# VLC_RX_Schem.net
KiCad netlist of a schematic drawn in Altium Designer
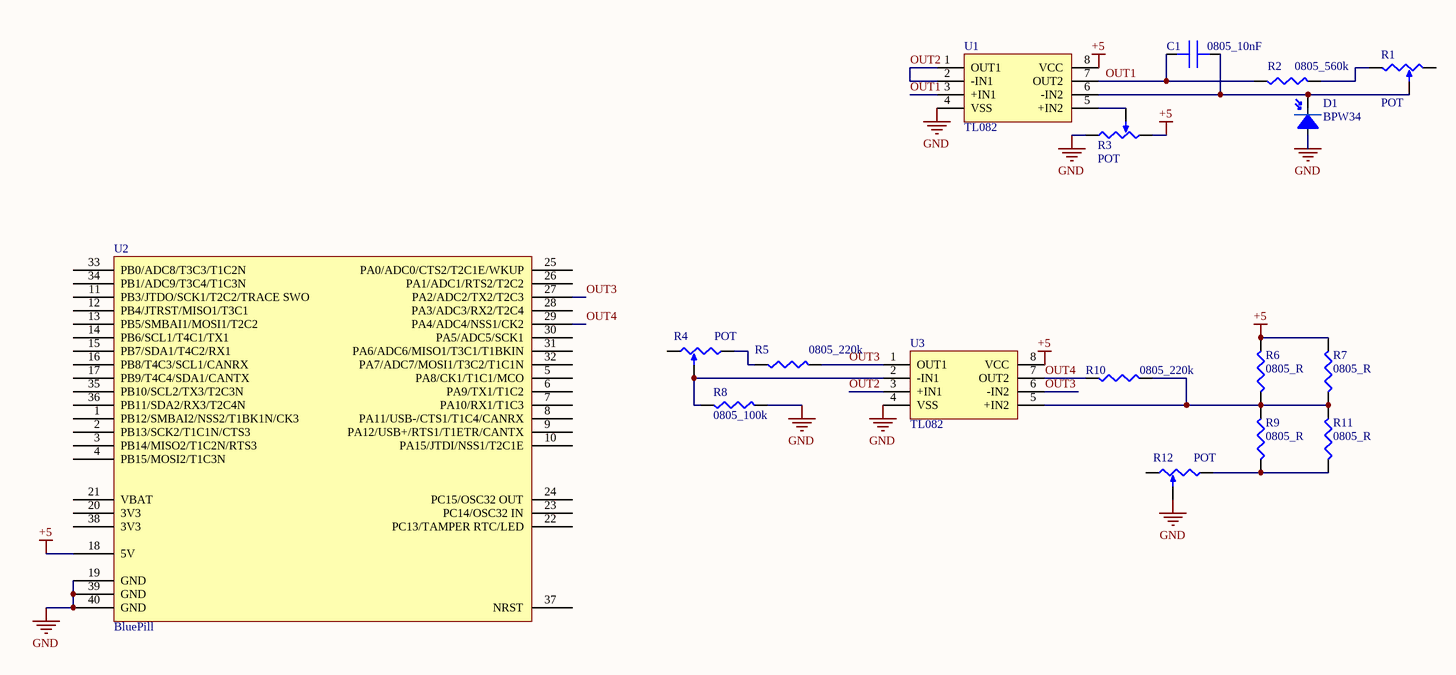
[diagram p0: VLC_RX_Schem.SchDoc]

(export (version "E")
  (design (tool "Eeschema 10.0.6"))
  (components
    (comp (ref "C1")
      (value "0805_10nF")
      (footprint "C0805 - 0.1uf")
      (description "0805 Capacitor")
      (libsource (lib "TimerSMD_Components") (part "0805 Capacitor"))
    )
    (comp (ref "D1") (value "BPW34") (footprint "BPW34") (libsource (lib "CAD_Symbols") (part "BPW34")))
    (comp (ref "R1") (value "POT") (footprint "POT 3386P") (libsource (lib "CAD_Symbols") (part "POT")))
    (comp (ref "R2")
      (value "0805_560k")
      (footprint "R0805")
      (libsource (lib "TimerSMD_Components") (part "0805 Resistor"))
    )
    (comp (ref "R3") (value "POT") (footprint "POT 3386P") (libsource (lib "CAD_Symbols") (part "POT")))
    (comp (ref "R4") (value "POT") (footprint "POT 3386P") (libsource (lib "CAD_Symbols") (part "POT")))
    (comp (ref "R5")
      (value "0805_220k")
      (footprint "R0805")
      (libsource (lib "TimerSMD_Components") (part "0805 Resistor"))
    )
    (comp (ref "R6")
      (value "0805_R")
      (footprint "R0805")
      (libsource (lib "TimerSMD_Components") (part "0805 Resistor"))
    )
    (comp (ref "R7")
      (value "0805_R")
      (footprint "R0805")
      (libsource (lib "TimerSMD_Components") (part "0805 Resistor"))
    )
    (comp (ref "R8")
      (value "0805_100k")
      (footprint "R0805")
      (libsource (lib "TimerSMD_Components") (part "0805 Resistor"))
    )
    (comp (ref "R9")
      (value "0805_R")
      (footprint "R0805")
      (libsource (lib "TimerSMD_Components") (part "0805 Resistor"))
    )
    (comp (ref "R10")
      (value "0805_220k")
      (footprint "R0805")
      (libsource (lib "TimerSMD_Components") (part "0805 Resistor"))
    )
    (comp (ref "R11")
      (value "0805_R")
      (footprint "R0805")
      (libsource (lib "TimerSMD_Components") (part "0805 Resistor"))
    )
    (comp (ref "R12") (value "POT") (footprint "POT 3386P") (libsource (lib "CAD_Symbols") (part "POT")))
    (comp (ref "U1")
      (value "TL082")
      (footprint "SOP8")
      (description "TL082CD SO-8 Operational Amplifier SMD IC")
      (libsource (lib "TimerSMD_Components") (part "TL082"))
    )
    (comp (ref "U2")
      (value "BluePill")
      (footprint "BluePill")
      (libsource (lib "CAD_Symbols") (part "STM32 BluePill"))
    )
    (comp (ref "U3")
      (value "TL082")
      (footprint "SOP8")
      (description "TL082CD SO-8 Operational Amplifier SMD IC")
      (libsource (lib "TimerSMD_Components") (part "TL082"))
    )
  )
  (nets
    (net (code "1") (name "+5") (class "Default")
      (node (ref "R3") (pin "1") (pinfunction "1_1") (pintype "passive"))
      (node (ref "R6") (pin "1") (pinfunction "1_1") (pintype "passive"))
      (node (ref "R7") (pin "1") (pinfunction "1_1") (pintype "passive"))
      (node (ref "U1") (pin "8") (pinfunction "VCC_8") (pintype "passive"))
      (node (ref "U2") (pin "18") (pinfunction "5V_18") (pintype "passive"))
      (node (ref "U3") (pin "8") (pinfunction "VCC_8") (pintype "passive"))
    )
    (net (code "2") (name "/OUT1") (class "Default")
      (node (ref "C1") (pin "1") (pinfunction "1_1") (pintype "passive"))
      (node (ref "R2") (pin "1") (pinfunction "1_1") (pintype "passive"))
      (node (ref "U1") (pin "3") (pinfunction "+IN1_3") (pintype "passive"))
      (node (ref "U1") (pin "7") (pinfunction "OUT2_7") (pintype "passive"))
    )
    (net (code "3") (name "/OUT2") (class "Default")
      (node (ref "U1") (pin "1") (pinfunction "OUT1_1") (pintype "passive"))
      (node (ref "U1") (pin "2") (pinfunction "-IN1_2") (pintype "passive"))
      (node (ref "U3") (pin "3") (pinfunction "+IN1_3") (pintype "passive"))
    )
    (net (code "4") (name "/OUT3") (class "Default")
      (node (ref "R5") (pin "1") (pinfunction "1_1") (pintype "passive"))
      (node (ref "U2") (pin "27") (pinfunction "PA2/ADC2/TX2/T2C3_27") (pintype "passive"))
      (node (ref "U3") (pin "1") (pinfunction "OUT1_1") (pintype "passive"))
      (node (ref "U3") (pin "6") (pinfunction "-IN2_6") (pintype "passive"))
    )
    (net (code "5") (name "/OUT4") (class "Default")
      (node (ref "R10") (pin "1") (pinfunction "1_1") (pintype "passive"))
      (node (ref "U2") (pin "29") (pinfunction "PA4/ADC4/NSS1/CK2_29") (pintype "passive"))
      (node (ref "U3") (pin "7") (pinfunction "OUT2_7") (pintype "passive"))
    )
    (net (code "6") (name "GND") (class "Default")
      (node (ref "D1") (pin "A") (pinfunction "Anode_A") (pintype "passive"))
      (node (ref "R12") (pin "3") (pinfunction "3_3") (pintype "passive"))
      (node (ref "R3") (pin "2") (pinfunction "2_2") (pintype "passive"))
      (node (ref "R8") (pin "2") (pinfunction "2_2") (pintype "passive"))
      (node (ref "U1") (pin "4") (pinfunction "VSS_4") (pintype "passive"))
      (node (ref "U2") (pin "19") (pinfunction "GND_19") (pintype "passive"))
      (node (ref "U2") (pin "39") (pinfunction "GND_39") (pintype "passive"))
      (node (ref "U2") (pin "40") (pinfunction "GND_40") (pintype "passive"))
      (node (ref "U3") (pin "4") (pinfunction "VSS_4") (pintype "passive"))
    )
    (net (code "7") (name "Net-(D1-Cathode)") (class "Default")
      (node (ref "C1") (pin "2") (pinfunction "2_2") (pintype "passive"))
      (node (ref "D1") (pin "K") (pinfunction "Cathode_K") (pintype "passive"))
      (node (ref "R1") (pin "3") (pinfunction "3_3") (pintype "passive"))
      (node (ref "U1") (pin "6") (pinfunction "-IN2_6") (pintype "passive"))
    )
    (net (code "8") (name "Net-(R1-Pad2)") (class "Default")
      (node (ref "R1") (pin "2") (pinfunction "2_2") (pintype "passive"))
      (node (ref "R2") (pin "2") (pinfunction "2_2") (pintype "passive"))
    )
    (net (code "9") (name "Net-(R4-Pad2)") (class "Default")
      (node (ref "R4") (pin "2") (pinfunction "2_2") (pintype "passive"))
      (node (ref "R5") (pin "2") (pinfunction "2_2") (pintype "passive"))
    )
    (net (code "10") (name "Net-(R11-Pad2)") (class "Default")
      (node (ref "R11") (pin "2") (pinfunction "2_2") (pintype "passive"))
      (node (ref "R12") (pin "2") (pinfunction "2_2") (pintype "passive"))
      (node (ref "R9") (pin "2") (pinfunction "2_2") (pintype "passive"))
    )
    (net (code "11") (name "Net-(U1-+IN2)") (class "Default")
      (node (ref "R3") (pin "3") (pinfunction "3_3") (pintype "passive"))
      (node (ref "U1") (pin "5") (pinfunction "+IN2_5") (pintype "passive"))
    )
    (net (code "12") (name "Net-(U3-+IN2)") (class "Default")
      (node (ref "R10") (pin "2") (pinfunction "2_2") (pintype "passive"))
      (node (ref "R11") (pin "1") (pinfunction "1_1") (pintype "passive"))
      (node (ref "R6") (pin "2") (pinfunction "2_2") (pintype "passive"))
      (node (ref "R7") (pin "2") (pinfunction "2_2") (pintype "passive"))
      (node (ref "R9") (pin "1") (pinfunction "1_1") (pintype "passive"))
      (node (ref "U3") (pin "5") (pinfunction "+IN2_5") (pintype "passive"))
    )
    (net (code "13") (name "Net-(U3--IN1)") (class "Default")
      (node (ref "R4") (pin "3") (pinfunction "3_3") (pintype "passive"))
      (node (ref "R8") (pin "1") (pinfunction "1_1") (pintype "passive"))
      (node (ref "U3") (pin "2") (pinfunction "-IN1_2") (pintype "passive"))
    )
    (net (code "14") (name "unconnected-(R1-Pad1)") (class "Default")
      (node (ref "R1") (pin "1") (pinfunction "1_1") (pintype "passive"))
    )
    (net (code "15") (name "unconnected-(R4-Pad1)") (class "Default")
      (node (ref "R4") (pin "1") (pinfunction "1_1") (pintype "passive"))
    )
    (net (code "16") (name "unconnected-(R12-Pad1)") (class "Default")
      (node (ref "R12") (pin "1") (pinfunction "1_1") (pintype "passive"))
    )
    (net (code "17") (name "unconnected-(U2-3V3-Pad20)") (class "Default")
      (node (ref "U2") (pin "20") (pinfunction "3V3_20") (pintype "passive"))
    )
    (net (code "18") (name "unconnected-(U2-3V3-Pad38)") (class "Default")
      (node (ref "U2") (pin "38") (pinfunction "3V3_38") (pintype "passive"))
    )
    (net (code "19") (name "unconnected-(U2-NRST-Pad37)") (class "Default")
      (node (ref "U2") (pin "37") (pinfunction "NRST_37") (pintype "passive"))
    )
    (net (code "20") (name "unconnected-(U2-PA0{slash}ADC0{slash}CTS2{slash}T2C1E{slash}WKUP-Pad25)") (class "Default")
      (node (ref "U2") (pin "25") (pinfunction "PA0/ADC0/CTS2/T2C1E/WKUP_25") (pintype "passive"))
    )
    (net (code "21") (name "unconnected-(U2-PA1{slash}ADC1{slash}RTS2{slash}T2C2-Pad26)") (class "Default")
      (node (ref "U2") (pin "26") (pinfunction "PA1/ADC1/RTS2/T2C2_26") (pintype "passive"))
    )
    (net (code "22") (name "unconnected-(U2-PA3{slash}ADC3{slash}RX2{slash}T2C4-Pad28)") (class "Default")
      (node (ref "U2") (pin "28") (pinfunction "PA3/ADC3/RX2/T2C4_28") (pintype "passive"))
    )
    (net (code "23") (name "unconnected-(U2-PA5{slash}ADC5{slash}SCK1-Pad30)") (class "Default")
      (node (ref "U2") (pin "30") (pinfunction "PA5/ADC5/SCK1_30") (pintype "passive"))
    )
    (net (code "24") (name "unconnected-(U2-PA6{slash}ADC6{slash}MISO1{slash}T3C1{slash}T1BKIN-Pad31)") (class "Default")
      (node (ref "U2") (pin "31") (pinfunction "PA6/ADC6/MISO1/T3C1/T1BKIN_31") (pintype "passive"))
    )
    (net (code "25") (name "unconnected-(U2-PA7{slash}ADC7{slash}MOSI1{slash}T3C2{slash}T1C1N-Pad32)") (class "Default")
      (node (ref "U2") (pin "32") (pinfunction "PA7/ADC7/MOSI1/T3C2/T1C1N_32") (pintype "passive"))
    )
    (net (code "26") (name "unconnected-(U2-PA8{slash}CK1{slash}T1C1{slash}MCO-Pad5)") (class "Default")
      (node (ref "U2") (pin "5") (pinfunction "PA8/CK1/T1C1/MCO_5") (pintype "passive"))
    )
    (net (code "27") (name "unconnected-(U2-PA9{slash}TX1{slash}T1C2-Pad6)") (class "Default")
      (node (ref "U2") (pin "6") (pinfunction "PA9/TX1/T1C2_6") (pintype "passive"))
    )
    (net (code "28") (name "unconnected-(U2-PA10{slash}RX1{slash}T1C3-Pad7)") (class "Default")
      (node (ref "U2") (pin "7") (pinfunction "PA10/RX1/T1C3_7") (pintype "passive"))
    )
    (net (code "29") (name "unconnected-(U2-PA11{slash}USB-{slash}CTS1{slash}T1C4{slash}CANRX-Pad8)") (class "Default")
      (node (ref "U2") (pin "8") (pinfunction "PA11/USB-/CTS1/T1C4/CANRX_8") (pintype "passive"))
    )
    (net (code "30") (name "unconnected-(U2-PA12{slash}USB+{slash}RTS1{slash}T1ETR{slash}CANTX-Pad9)") (class "Default")
      (node (ref "U2") (pin "9") (pinfunction "PA12/USB+/RTS1/T1ETR/CANTX_9") (pintype "passive"))
    )
    (net (code "31") (name "unconnected-(U2-PA15{slash}JTDI{slash}NSS1{slash}T2C1E-Pad10)") (class "Default")
      (node (ref "U2") (pin "10") (pinfunction "PA15/JTDI/NSS1/T2C1E_10") (pintype "passive"))
    )
    (net (code "32") (name "unconnected-(U2-PB0{slash}ADC8{slash}T3C3{slash}T1C2N-Pad33)") (class "Default")
      (node (ref "U2") (pin "33") (pinfunction "PB0/ADC8/T3C3/T1C2N_33") (pintype "passive"))
    )
    (net (code "33") (name "unconnected-(U2-PB1{slash}ADC9{slash}T3C4{slash}T1C3N-Pad34)") (class "Default")
      (node (ref "U2") (pin "34") (pinfunction "PB1/ADC9/T3C4/T1C3N_34") (pintype "passive"))
    )
    (net (code "34") (name "unconnected-(U2-PB3{slash}JTDO{slash}SCK1{slash}T2C2{slash}TRACE_SWO-Pad11)") (class "Default")
      (node (ref "U2") (pin "11") (pinfunction "PB3/JTDO/SCK1/T2C2/TRACE_SWO_11") (pintype "passive"))
    )
    (net (code "35") (name "unconnected-(U2-PB4{slash}JTRST{slash}MISO1{slash}T3C1-Pad12)") (class "Default")
      (node (ref "U2") (pin "12") (pinfunction "PB4/JTRST/MISO1/T3C1_12") (pintype "passive"))
    )
    (net (code "36") (name "unconnected-(U2-PB5{slash}SMBAI1{slash}MOSI1{slash}T2C2-Pad13)") (class "Default")
      (node (ref "U2") (pin "13") (pinfunction "PB5/SMBAI1/MOSI1/T2C2_13") (pintype "passive"))
    )
    (net (code "37") (name "unconnected-(U2-PB6{slash}SCL1{slash}T4C1{slash}TX1-Pad14)") (class "Default")
      (node (ref "U2") (pin "14") (pinfunction "PB6/SCL1/T4C1/TX1_14") (pintype "passive"))
    )
    (net (code "38") (name "unconnected-(U2-PB7{slash}SDA1{slash}T4C2{slash}RX1-Pad15)") (class "Default")
      (node (ref "U2") (pin "15") (pinfunction "PB7/SDA1/T4C2/RX1_15") (pintype "passive"))
    )
    (net (code "39") (name "unconnected-(U2-PB8{slash}T4C3{slash}SCL1{slash}CANRX-Pad16)") (class "Default")
      (node (ref "U2") (pin "16") (pinfunction "PB8/T4C3/SCL1/CANRX_16") (pintype "passive"))
    )
    (net (code "40") (name "unconnected-(U2-PB9{slash}T4C4{slash}SDA1{slash}CANTX-Pad17)") (class "Default")
      (node (ref "U2") (pin "17") (pinfunction "PB9/T4C4/SDA1/CANTX_17") (pintype "passive"))
    )
    (net (code "41") (name "unconnected-(U2-PB10{slash}SCL2{slash}TX3{slash}T2C3N-Pad35)") (class "Default")
      (node (ref "U2") (pin "35") (pinfunction "PB10/SCL2/TX3/T2C3N_35") (pintype "passive"))
    )
    (net (code "42") (name "unconnected-(U2-PB11{slash}SDA2{slash}RX3{slash}T2C4N-Pad36)") (class "Default")
      (node (ref "U2") (pin "36") (pinfunction "PB11/SDA2/RX3/T2C4N_36") (pintype "passive"))
    )
    (net (code "43") (name "unconnected-(U2-PB12{slash}SMBAI2{slash}NSS2{slash}T1BK1N{slash}CK3-Pad1)") (class "Default")
      (node (ref "U2") (pin "1") (pinfunction "PB12/SMBAI2/NSS2/T1BK1N/CK3_1") (pintype "passive"))
    )
    (net (code "44") (name "unconnected-(U2-PB13{slash}SCK2{slash}T1C1N{slash}CTS3-Pad2)") (class "Default")
      (node (ref "U2") (pin "2") (pinfunction "PB13/SCK2/T1C1N/CTS3_2") (pintype "passive"))
    )
    (net (code "45") (name "unconnected-(U2-PB14{slash}MISO2{slash}T1C2N{slash}RTS3-Pad3)") (class "Default")
      (node (ref "U2") (pin "3") (pinfunction "PB14/MISO2/T1C2N/RTS3_3") (pintype "passive"))
    )
    (net (code "46") (name "unconnected-(U2-PB15{slash}MOSI2{slash}T1C3N-Pad4)") (class "Default")
      (node (ref "U2") (pin "4") (pinfunction "PB15/MOSI2/T1C3N_4") (pintype "passive"))
    )
    (net (code "47") (name "unconnected-(U2-PC13{slash}TAMPER_RTC{slash}LED-Pad22)") (class "Default")
      (node (ref "U2") (pin "22") (pinfunction "PC13/TAMPER_RTC/LED_22") (pintype "passive"))
    )
    (net (code "48") (name "unconnected-(U2-PC14{slash}OSC32_IN-Pad23)") (class "Default")
      (node (ref "U2") (pin "23") (pinfunction "PC14/OSC32_IN_23") (pintype "passive"))
    )
    (net (code "49") (name "unconnected-(U2-PC15{slash}OSC32_OUT-Pad24)") (class "Default")
      (node (ref "U2") (pin "24") (pinfunction "PC15/OSC32_OUT_24") (pintype "passive"))
    )
    (net (code "50") (name "unconnected-(U2-VBAT-Pad21)") (class "Default")
      (node (ref "U2") (pin "21") (pinfunction "VBAT_21") (pintype "passive"))
    )
  )
)
